# External_connections.net
KiCad netlist of a schematic drawn in Altium Designer
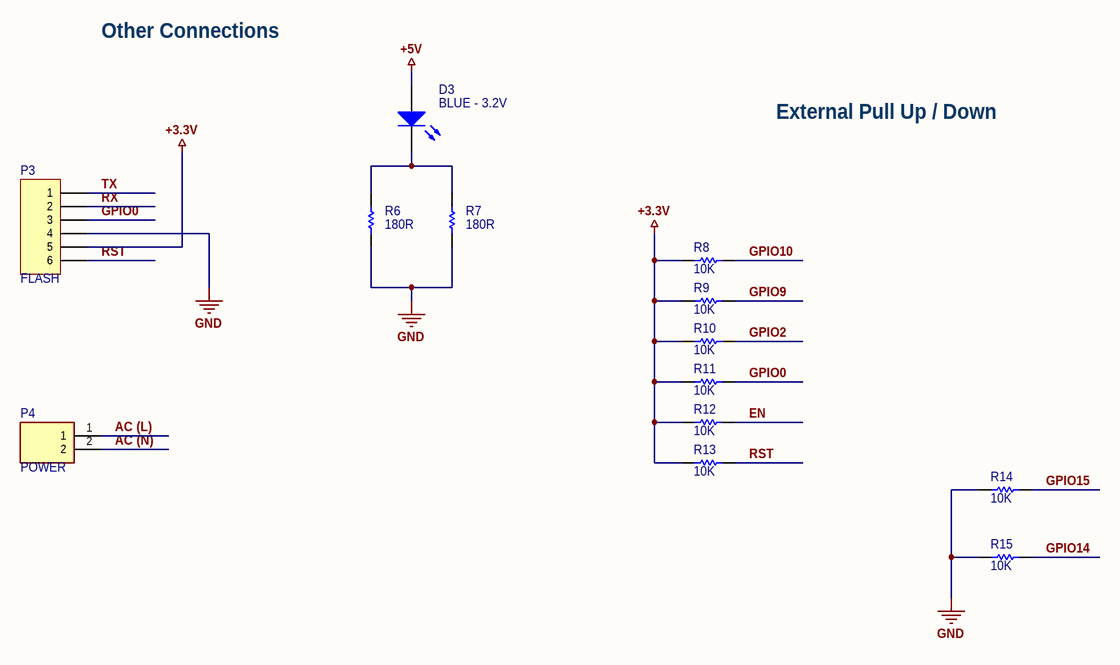
[diagram p0: External connections.SchDoc]

(export (version "E")
  (design (tool "Eeschema 10.0.6"))
  (components
    (comp (ref "D3")
      (value "BLUE - 3.2V")
      (footprint "3528")
      (description "SMD mono-color Top LED, WL-SMTW, Blue")
      (fields (field (name "PARTNUMBER") "150141BS73100") (field (name "MANUFACTURER") "Wuerth Elektronik"))
      (libsource (lib "Altium Content Vault") (part "WE-LED_K1A2-2"))
    )
    (comp (ref "P3")
      (value "FLASH")
      (footprint "My_1X06")
      (description "Header, 6-Pin")
      (fields (field (name "ASID PART NUMBER") "Header 6-AS"))
      (libsource (lib "Mylib+Rev+4") (part "Header 6"))
    )
    (comp (ref "P4")
      (value "POWER")
      (footprint "SamacSys:TB00250002BE")
      (description "Connector")
      (fields
        (field (name "MANUFACTURER_PART_NUMBER") "TB002-500-02BE")
        (field (name "MOUSER PART NUMBER") "490-TB002-500-02BE")
      )
      (libsource (lib "*") (part "TB002-500-02BE"))
    )
    (comp (ref "R6")
      (value "180R")
      (footprint "RESC2013X60X35ML10T20")
      (description "Res Thick Film 0805 180R Ohm 1% 0.125W(1/8W) +/-100ppm/C Epoxy Pad SMD T/R")
      (libsource (lib "University of Moratuwa") (part "RES-2"))
    )
    (comp (ref "R7")
      (value "180R")
      (footprint "RESC2013X60X35ML10T20")
      (description "Res Thick Film 0805 180R Ohm 1% 0.125W(1/8W) +/-100ppm/C Epoxy Pad SMD T/R")
      (libsource (lib "University of Moratuwa") (part "RES-2"))
    )
    (comp (ref "R8")
      (value "10K")
      (footprint "RESC2013X60X35ML10T20")
      (description "Res Thick Film 0805 10K Ohm 1% 0.125W(1/8W) +/-100ppm/C Epoxy Pad SMD T/R")
      (libsource (lib "University of Moratuwa") (part "RES-2"))
    )
    (comp (ref "R9")
      (value "10K")
      (footprint "RESC2013X60X35ML10T20")
      (description "Res Thick Film 0805 10K Ohm 1% 0.125W(1/8W) +/-100ppm/C Epoxy Pad SMD T/R")
      (libsource (lib "University of Moratuwa") (part "RES-2"))
    )
    (comp (ref "R10")
      (value "10K")
      (footprint "RESC2013X60X35ML10T20")
      (description "Res Thick Film 0805 10K Ohm 1% 0.125W(1/8W) +/-100ppm/C Epoxy Pad SMD T/R")
      (libsource (lib "University of Moratuwa") (part "RES-2"))
    )
    (comp (ref "R11")
      (value "10K")
      (footprint "RESC2013X60X35ML10T20")
      (description "Res Thick Film 0805 10K Ohm 1% 0.125W(1/8W) +/-100ppm/C Epoxy Pad SMD T/R")
      (libsource (lib "University of Moratuwa") (part "RES-2"))
    )
    (comp (ref "R12")
      (value "10K")
      (footprint "RESC2013X60X35ML10T20")
      (description "Res Thick Film 0805 10K Ohm 1% 0.125W(1/8W) +/-100ppm/C Epoxy Pad SMD T/R")
      (libsource (lib "University of Moratuwa") (part "RES-2"))
    )
    (comp (ref "R13")
      (value "10K")
      (footprint "RESC2013X60X35ML10T20")
      (description "Res Thick Film 0805 10K Ohm 1% 0.125W(1/8W) +/-100ppm/C Epoxy Pad SMD T/R")
      (libsource (lib "University of Moratuwa") (part "RES-2"))
    )
    (comp (ref "R14")
      (value "10K")
      (footprint "RESC2013X60X35ML10T20")
      (description "Res Thick Film 0805 10K Ohm 1% 0.125W(1/8W) +/-100ppm/C Epoxy Pad SMD T/R")
      (libsource (lib "University of Moratuwa") (part "RES-2"))
    )
    (comp (ref "R15")
      (value "10K")
      (footprint "RESC2013X60X35ML10T20")
      (description "Res Thick Film 0805 10K Ohm 1% 0.125W(1/8W) +/-100ppm/C Epoxy Pad SMD T/R")
      (libsource (lib "University of Moratuwa") (part "RES-2"))
    )
  )
  (nets
    (net (code "1") (name "+3.3V") (class "Default")
      (node (ref "P3") (pin "5") (pinfunction "5_5") (pintype "passive"))
      (node (ref "R10") (pin "2") (pinfunction "2_2") (pintype "passive"))
      (node (ref "R11") (pin "2") (pinfunction "2_2") (pintype "passive"))
      (node (ref "R12") (pin "1") (pinfunction "1_1") (pintype "passive"))
      (node (ref "R13") (pin "1") (pinfunction "1_1") (pintype "passive"))
      (node (ref "R8") (pin "2") (pinfunction "2_2") (pintype "passive"))
      (node (ref "R9") (pin "2") (pinfunction "2_2") (pintype "passive"))
    )
    (net (code "2") (name "+5V") (class "Default")
      (node (ref "D3") (pin "2") (pinfunction "A_2") (pintype "passive"))
    )
    (net (code "3") (name "/AC (L)") (class "Default")
      (node (ref "P4") (pin "1") (pinfunction "1_1") (pintype "passive"))
    )
    (net (code "4") (name "/AC (N)") (class "Default")
      (node (ref "P4") (pin "2") (pinfunction "2_2") (pintype "passive"))
    )
    (net (code "5") (name "/EN") (class "Default")
      (node (ref "R12") (pin "2") (pinfunction "2_2") (pintype "passive"))
    )
    (net (code "6") (name "/GPIO0") (class "Default")
      (node (ref "P3") (pin "3") (pinfunction "3_3") (pintype "passive"))
      (node (ref "R11") (pin "1") (pinfunction "1_1") (pintype "passive"))
    )
    (net (code "7") (name "/GPIO2") (class "Default")
      (node (ref "R10") (pin "1") (pinfunction "1_1") (pintype "passive"))
    )
    (net (code "8") (name "/GPIO9") (class "Default")
      (node (ref "R9") (pin "1") (pinfunction "1_1") (pintype "passive"))
    )
    (net (code "9") (name "/GPIO10") (class "Default")
      (node (ref "R8") (pin "1") (pinfunction "1_1") (pintype "passive"))
    )
    (net (code "10") (name "/GPIO14") (class "Default")
      (node (ref "R15") (pin "1") (pinfunction "1_1") (pintype "passive"))
    )
    (net (code "11") (name "/GPIO15") (class "Default")
      (node (ref "R14") (pin "1") (pinfunction "1_1") (pintype "passive"))
    )
    (net (code "12") (name "/RST") (class "Default")
      (node (ref "P3") (pin "6") (pinfunction "6_6") (pintype "passive"))
      (node (ref "R13") (pin "2") (pinfunction "2_2") (pintype "passive"))
    )
    (net (code "13") (name "/RX") (class "Default")
      (node (ref "P3") (pin "2") (pinfunction "2_2") (pintype "passive"))
    )
    (net (code "14") (name "/TX") (class "Default")
      (node (ref "P3") (pin "1") (pinfunction "1_1") (pintype "passive"))
    )
    (net (code "15") (name "GND") (class "Default")
      (node (ref "P3") (pin "4") (pinfunction "4_4") (pintype "passive"))
      (node (ref "R14") (pin "2") (pinfunction "2_2") (pintype "passive"))
      (node (ref "R15") (pin "2") (pinfunction "2_2") (pintype "passive"))
      (node (ref "R6") (pin "2") (pinfunction "2_2") (pintype "passive"))
      (node (ref "R7") (pin "2") (pinfunction "2_2") (pintype "passive"))
    )
    (net (code "16") (name "Net-(D3-K)") (class "Default")
      (node (ref "D3") (pin "1") (pinfunction "K_1") (pintype "passive"))
      (node (ref "R6") (pin "1") (pinfunction "1_1") (pintype "passive"))
      (node (ref "R7") (pin "1") (pinfunction "1_1") (pintype "passive"))
    )
  )
)
